# rotator.net
KiCad netlist of a schematic drawn in EAGLE
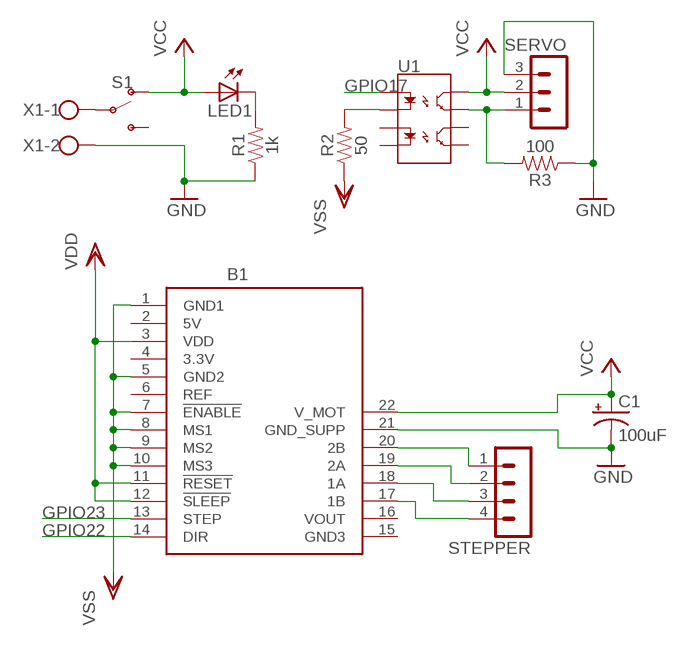
[diagram p0: schematic, sheet 1]

(export (version "E")
  (design (tool "Eeschema 10.0.6"))
  (components
    (comp (ref "B1")
      (value "POLOLU_1183")
      (footprint "eagle-import:POLOLU_1183")
      (libsource (lib "eagle-import") (part "POLOLU_1183"))
    )
    (comp (ref "C1")
      (value "100uF")
      (footprint "eagle-import:CPOL-RADIAL-2.5MM-6.5MM")
      (libsource (lib "eagle-import") (part "100UF-POLAR-RADIAL-2.5MM-25V-20%"))
    )
    (comp (ref "LED1")
      (value "LED")
      (footprint "eagle-import:SMARTLED-TTW")
      (libsource (lib "eagle-import") (part "LED"))
    )
    (comp (ref "R1")
      (value "1k")
      (footprint "eagle-import:0603")
      (libsource (lib "eagle-import") (part "1KOHM-0603-1/10W-1%"))
    )
    (comp (ref "R2")
      (value "50")
      (footprint "eagle-import:0603")
      (libsource (lib "eagle-import") (part "68OHM-0603-1/10W-1%"))
    )
    (comp (ref "R3")
      (value "100")
      (footprint "eagle-import:0603")
      (libsource (lib "eagle-import") (part "68OHM-0603-1/10W-1%"))
    )
    (comp (ref "S1")
      (value "SWITCH-SPDT-PTH-11.6X4.0MM")
      (footprint "eagle-import:SWITCH_SPDT_PTH_11.6X4.0MM")
      (libsource (lib "eagle-import") (part "SWITCH-SPDT-PTH-11.6X4.0MM"))
    )
    (comp (ref "SERVO")
      (value "MA03-1")
      (footprint "eagle-import:MA03-1")
      (libsource (lib "eagle-import") (part "MA03-1"))
    )
    (comp (ref "STEPPER")
      (value "MA04-1")
      (footprint "eagle-import:MA04-1")
      (libsource (lib "eagle-import") (part "MA04-1"))
    )
    (comp (ref "U1")
      (value "DUAL-OPTOISOLATOR_SOIC8")
      (footprint "eagle-import:SO08")
      (libsource (lib "eagle-import") (part "DUAL-OPTOISOLATOR_SOIC8"))
    )
    (comp (ref "X1")
      (value "W237-102")
      (footprint "eagle-import:W237-102")
      (fields (field (name "MPN") "237-102"))
      (libsource (lib "eagle-import") (part "W237-102"))
    )
  )
  (nets
    (net (code "1") (name "GND") (class "Default")
      (node (ref "B1") (pin "21") (pinfunction "GND_SUPP_21") (pintype "bidirectional"))
      (node (ref "C1") (pin "2") (pinfunction "-_2") (pintype "passive"))
      (node (ref "R1") (pin "1") (pinfunction "1_1") (pintype "passive"))
      (node (ref "R3") (pin "1") (pinfunction "1_1") (pintype "passive"))
      (node (ref "SERVO") (pin "3") (pinfunction "3_3") (pintype "passive"))
      (node (ref "X1") (pin "2") (pinfunction "KL_2") (pintype "passive"))
    )
    (net (code "2") (name "GPIO17") (class "Default")
      (node (ref "U1") (pin "1") (pinfunction "A1_1") (pintype "bidirectional"))
    )
    (net (code "3") (name "GPIO22") (class "Default")
      (node (ref "B1") (pin "14") (pinfunction "DIR_14") (pintype "bidirectional"))
    )
    (net (code "4") (name "GPIO23") (class "Default")
      (node (ref "B1") (pin "13") (pinfunction "STEP_13") (pintype "bidirectional"))
    )
    (net (code "5") (name "Net-(B1-1A)") (class "Default")
      (node (ref "B1") (pin "18") (pinfunction "1A_18") (pintype "bidirectional"))
      (node (ref "STEPPER") (pin "3") (pinfunction "3_3") (pintype "passive"))
    )
    (net (code "6") (name "Net-(B1-1B)") (class "Default")
      (node (ref "B1") (pin "17") (pinfunction "1B_17") (pintype "bidirectional"))
      (node (ref "STEPPER") (pin "4") (pinfunction "4_4") (pintype "passive"))
    )
    (net (code "7") (name "Net-(B1-2A)") (class "Default")
      (node (ref "B1") (pin "19") (pinfunction "2A_19") (pintype "bidirectional"))
      (node (ref "STEPPER") (pin "2") (pinfunction "2_2") (pintype "passive"))
    )
    (net (code "8") (name "Net-(B1-2B)") (class "Default")
      (node (ref "B1") (pin "20") (pinfunction "2B_20") (pintype "bidirectional"))
      (node (ref "STEPPER") (pin "1") (pinfunction "1_1") (pintype "passive"))
    )
    (net (code "9") (name "Net-(LED1-C)") (class "Default")
      (node (ref "LED1") (pin "C@1") (pinfunction "C_C@1") (pintype "passive"))
      (node (ref "R1") (pin "2") (pinfunction "2_2") (pintype "passive"))
    )
    (net (code "10") (name "Net-(S1-P)") (class "Default")
      (node (ref "S1") (pin "2") (pinfunction "P_2") (pintype "passive"))
      (node (ref "X1") (pin "1") (pinfunction "KL_1") (pintype "passive"))
    )
    (net (code "11") (name "Net-(U1-C1)") (class "Default")
      (node (ref "R2") (pin "2") (pinfunction "2_2") (pintype "passive"))
      (node (ref "U1") (pin "2") (pinfunction "C1_2") (pintype "bidirectional"))
    )
    (net (code "12") (name "Net-(U1-EM1)") (class "Default")
      (node (ref "R3") (pin "2") (pinfunction "2_2") (pintype "passive"))
      (node (ref "SERVO") (pin "1") (pinfunction "1_1") (pintype "passive"))
      (node (ref "U1") (pin "7") (pinfunction "EM1_7") (pintype "bidirectional"))
    )
    (net (code "13") (name "VCC") (class "Default")
      (node (ref "B1") (pin "22") (pinfunction "V_MOT_22") (pintype "bidirectional"))
      (node (ref "C1") (pin "1") (pinfunction "+_1") (pintype "passive"))
      (node (ref "LED1") (pin "A@1") (pinfunction "A_A@1") (pintype "passive"))
      (node (ref "S1") (pin "1") (pinfunction "O_1") (pintype "passive"))
      (node (ref "SERVO") (pin "2") (pinfunction "2_2") (pintype "passive"))
      (node (ref "U1") (pin "8") (pinfunction "CL1_8") (pintype "bidirectional"))
    )
    (net (code "14") (name "VDD") (class "Default")
      (node (ref "B1") (pin "11") (pinfunction "~{RESET}_11") (pintype "bidirectional"))
      (node (ref "B1") (pin "12") (pinfunction "~{SLEEP}_12") (pintype "bidirectional"))
      (node (ref "B1") (pin "3") (pinfunction "VDD_3") (pintype "bidirectional"))
    )
    (net (code "15") (name "VSS") (class "Default")
      (node (ref "B1") (pin "1") (pinfunction "GND1_1") (pintype "bidirectional"))
      (node (ref "B1") (pin "10") (pinfunction "MS3_10") (pintype "bidirectional"))
      (node (ref "B1") (pin "5") (pinfunction "GND2_5") (pintype "bidirectional"))
      (node (ref "B1") (pin "7") (pinfunction "~{ENABLE}_7") (pintype "bidirectional"))
      (node (ref "B1") (pin "8") (pinfunction "MS1_8") (pintype "bidirectional"))
      (node (ref "B1") (pin "9") (pinfunction "MS2_9") (pintype "bidirectional"))
      (node (ref "R2") (pin "1") (pinfunction "1_1") (pintype "passive"))
    )
    (net (code "16") (name "unconnected-(B1-3.3V-Pad4)") (class "Default")
      (node (ref "B1") (pin "4") (pinfunction "3.3V_4") (pintype "bidirectional"))
    )
    (net (code "17") (name "unconnected-(B1-5V-Pad2)") (class "Default")
      (node (ref "B1") (pin "2") (pinfunction "5V_2") (pintype "bidirectional"))
    )
    (net (code "18") (name "unconnected-(B1-GND3-Pad15)") (class "Default")
      (node (ref "B1") (pin "15") (pinfunction "GND3_15") (pintype "bidirectional"))
    )
    (net (code "19") (name "unconnected-(B1-REF-Pad6)") (class "Default")
      (node (ref "B1") (pin "6") (pinfunction "REF_6") (pintype "bidirectional"))
    )
    (net (code "20") (name "unconnected-(B1-VOUT-Pad16)") (class "Default")
      (node (ref "B1") (pin "16") (pinfunction "VOUT_16") (pintype "bidirectional"))
    )
    (net (code "21") (name "unconnected-(S1-S-Pad3)") (class "Default")
      (node (ref "S1") (pin "3") (pinfunction "S_3") (pintype "passive"))
    )
    (net (code "22") (name "unconnected-(U1-A2-Pad3)") (class "Default")
      (node (ref "U1") (pin "3") (pinfunction "A2_3") (pintype "bidirectional"))
    )
    (net (code "23") (name "unconnected-(U1-C2-Pad4)") (class "Default")
      (node (ref "U1") (pin "4") (pinfunction "C2_4") (pintype "bidirectional"))
    )
    (net (code "24") (name "unconnected-(U1-CL2-Pad6)") (class "Default")
      (node (ref "U1") (pin "6") (pinfunction "CL2_6") (pintype "bidirectional"))
    )
    (net (code "25") (name "unconnected-(U1-EM2-Pad5)") (class "Default")
      (node (ref "U1") (pin "5") (pinfunction "EM2_5") (pintype "bidirectional"))
    )
  )
)
